# tm4.net
KiCad netlist of a schematic drawn in EAGLE
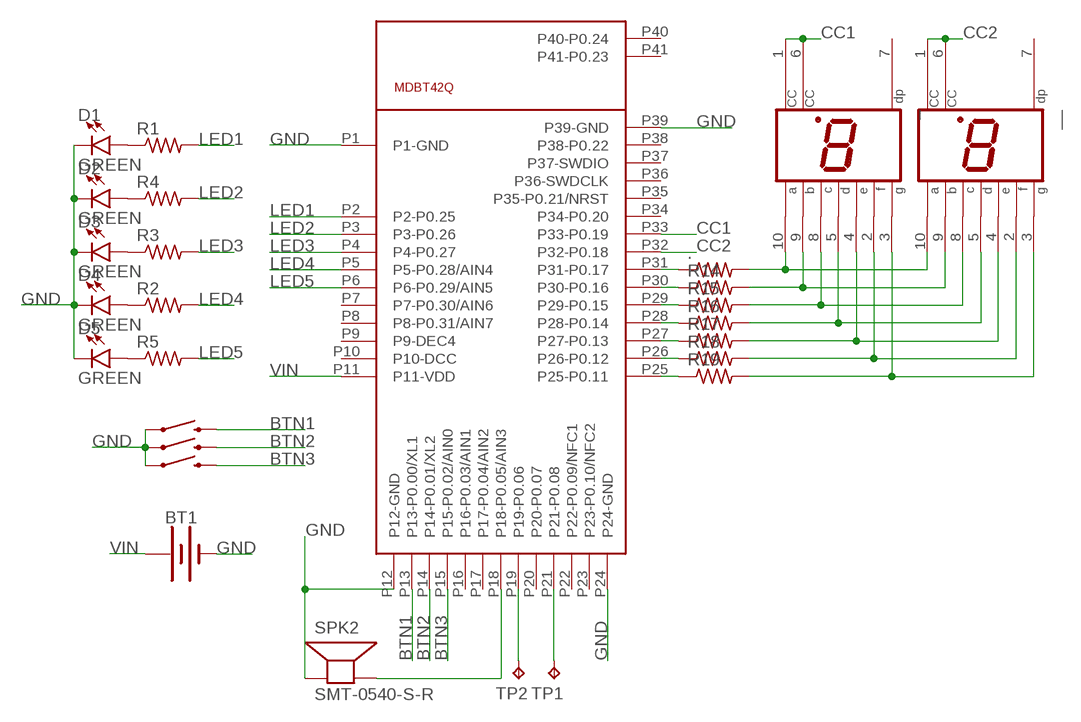
[diagram p0: schematic, sheet 1]

(export (version "E")
  (design (tool "Eeschema 10.0.6"))
  (components
    (comp (ref ".")
      (value "R-US_M0805")
      (footprint "eagle-import:M0805")
      (libsource (lib "eagle-import") (part "R-US_M0805"))
    )
    (comp (ref "BT1")
      (value "BATTERY-12MM_SMD")
      (footprint "eagle-import:BATTCON_12MM")
      (libsource (lib "eagle-import") (part "BATTERY-12MM_SMD"))
    )
    (comp (ref "D1")
      (value "GREEN")
      (footprint "eagle-import:LED-1206")
      (libsource (lib "eagle-import") (part "LED-GREEN1206"))
    )
    (comp (ref "D2")
      (value "GREEN")
      (footprint "eagle-import:LED-1206")
      (libsource (lib "eagle-import") (part "LED-GREEN1206"))
    )
    (comp (ref "D3")
      (value "GREEN")
      (footprint "eagle-import:LED-1206")
      (libsource (lib "eagle-import") (part "LED-GREEN1206"))
    )
    (comp (ref "D4")
      (value "GREEN")
      (footprint "eagle-import:LED-1206")
      (libsource (lib "eagle-import") (part "LED-GREEN1206"))
    )
    (comp (ref "D5")
      (value "GREEN")
      (footprint "eagle-import:LED-1206")
      (libsource (lib "eagle-import") (part "LED-GREEN1206"))
    )
    (comp (ref "R1")
      (value "R-US_M0805")
      (footprint "eagle-import:M0805")
      (libsource (lib "eagle-import") (part "R-US_M0805"))
    )
    (comp (ref "R2")
      (value "R-US_M0805")
      (footprint "eagle-import:M0805")
      (libsource (lib "eagle-import") (part "R-US_M0805"))
    )
    (comp (ref "R3")
      (value "R-US_M0805")
      (footprint "eagle-import:M0805")
      (libsource (lib "eagle-import") (part "R-US_M0805"))
    )
    (comp (ref "R4")
      (value "R-US_M0805")
      (footprint "eagle-import:M0805")
      (libsource (lib "eagle-import") (part "R-US_M0805"))
    )
    (comp (ref "R5")
      (value "R-US_M0805")
      (footprint "eagle-import:M0805")
      (libsource (lib "eagle-import") (part "R-US_M0805"))
    )
    (comp (ref "R14")
      (value "R-US_M0805")
      (footprint "eagle-import:M0805")
      (libsource (lib "eagle-import") (part "R-US_M0805"))
    )
    (comp (ref "R15")
      (value "R-US_M0805")
      (footprint "eagle-import:M0805")
      (libsource (lib "eagle-import") (part "R-US_M0805"))
    )
    (comp (ref "R16")
      (value "R-US_M0805")
      (footprint "eagle-import:M0805")
      (libsource (lib "eagle-import") (part "R-US_M0805"))
    )
    (comp (ref "R17")
      (value "R-US_M0805")
      (footprint "eagle-import:M0805")
      (libsource (lib "eagle-import") (part "R-US_M0805"))
    )
    (comp (ref "R18")
      (value "R-US_M0805")
      (footprint "eagle-import:M0805")
      (libsource (lib "eagle-import") (part "R-US_M0805"))
    )
    (comp (ref "R19")
      (value "R-US_M0805")
      (footprint "eagle-import:M0805")
      (libsource (lib "eagle-import") (part "R-US_M0805"))
    )
    (comp (ref "SPK2")
      (value "SMT-0540-S-R")
      (footprint "eagle-import:SMT-0540-S-R")
      (libsource (lib "eagle-import") (part "SMT-0540-S-R"))
    )
    (comp (ref "TP1")
      (value "TPTP19R")
      (footprint "eagle-import:TP19R")
      (libsource (lib "eagle-import") (part "TPTP19R"))
    )
    (comp (ref "TP2")
      (value "TPTP19R")
      (footprint "eagle-import:TP19R")
      (libsource (lib "eagle-import") (part "TPTP19R"))
    )
    (comp (ref "U$1")
      (value "MDBT42Q")
      (footprint "eagle-import:MDBT40")
      (libsource (lib "eagle-import") (part "MDBT42Q"))
    )
    (comp (ref "_")
      (value "HD-A103")
      (footprint "eagle-import:HDSP-A")
      (libsource (lib "eagle-import") (part "HD-A103"))
    )
    (comp (ref "__")
      (value "HD-A103")
      (footprint "eagle-import:HDSP-A")
      (libsource (lib "eagle-import") (part "HD-A103"))
    )
    (comp (ref "____")
      (value "MOMENTARY-SWITCH-SPST-SMD-6.2MM-TALL")
      (footprint "eagle-import:TACTILE_SWITCH_SMD_6.2MM_TALL")
      (libsource (lib "eagle-import") (part "MOMENTARY-SWITCH-SPST-SMD-6.2MM-TALL"))
    )
    (comp (ref "_____")
      (value "MOMENTARY-SWITCH-SPST-SMD-6.2MM-TALL")
      (footprint "eagle-import:TACTILE_SWITCH_SMD_6.2MM_TALL")
      (libsource (lib "eagle-import") (part "MOMENTARY-SWITCH-SPST-SMD-6.2MM-TALL"))
    )
    (comp (ref "______")
      (value "MOMENTARY-SWITCH-SPST-SMD-6.2MM-TALL")
      (footprint "eagle-import:TACTILE_SWITCH_SMD_6.2MM_TALL")
      (libsource (lib "eagle-import") (part "MOMENTARY-SWITCH-SPST-SMD-6.2MM-TALL"))
    )
  )
  (nets
    (net (code "1") (name "/BTN1") (class "Default")
      (node (ref "U$1") (pin "P13") (pinfunction "P13-P0.00/XL1_P13") (pintype "bidirectional"))
      (node (ref "____") (pin "B2") (pinfunction "2_B2") (pintype "passive"))
    )
    (net (code "2") (name "/BTN2") (class "Default")
      (node (ref "U$1") (pin "P14") (pinfunction "P14-P0.01/XL2_P14") (pintype "bidirectional"))
      (node (ref "_____") (pin "B2") (pinfunction "2_B2") (pintype "passive"))
    )
    (net (code "3") (name "/BTN3") (class "Default")
      (node (ref "U$1") (pin "P15") (pinfunction "P15-P0.02/AIN0_P15") (pintype "bidirectional"))
      (node (ref "______") (pin "B2") (pinfunction "2_B2") (pintype "passive"))
    )
    (net (code "4") (name "/CC1") (class "Default")
      (node (ref "U$1") (pin "P33") (pinfunction "P33-P0.19_P33") (pintype "bidirectional"))
      (node (ref "_") (pin "1") (pinfunction "CC_1") (pintype "passive"))
      (node (ref "_") (pin "6") (pinfunction "CC_6") (pintype "passive"))
    )
    (net (code "5") (name "/CC2") (class "Default")
      (node (ref "U$1") (pin "P32") (pinfunction "P32-P0.18_P32") (pintype "bidirectional"))
      (node (ref "__") (pin "1") (pinfunction "CC_1") (pintype "passive"))
      (node (ref "__") (pin "6") (pinfunction "CC_6") (pintype "passive"))
    )
    (net (code "6") (name "/GND") (class "Default")
      (node (ref "BT1") (pin "GND") (pinfunction "-_GND") (pintype "power_in"))
      (node (ref "D1") (pin "C") (pinfunction "C_C") (pintype "passive"))
      (node (ref "D2") (pin "C") (pinfunction "C_C") (pintype "passive"))
      (node (ref "D3") (pin "C") (pinfunction "C_C") (pintype "passive"))
      (node (ref "D4") (pin "C") (pinfunction "C_C") (pintype "passive"))
      (node (ref "D5") (pin "C") (pinfunction "C_C") (pintype "passive"))
      (node (ref "SPK2") (pin "-") (pinfunction "+_-") (pintype "passive"))
      (node (ref "U$1") (pin "P1") (pinfunction "P1-GND_P1") (pintype "bidirectional"))
      (node (ref "U$1") (pin "P12") (pinfunction "P12-GND_P12") (pintype "bidirectional"))
      (node (ref "U$1") (pin "P24") (pinfunction "P24-GND_P24") (pintype "bidirectional"))
      (node (ref "U$1") (pin "P39") (pinfunction "P39-GND_P39") (pintype "bidirectional"))
      (node (ref "____") (pin "A2") (pinfunction "1_A2") (pintype "passive"))
      (node (ref "_____") (pin "A2") (pinfunction "1_A2") (pintype "passive"))
      (node (ref "______") (pin "A2") (pinfunction "1_A2") (pintype "passive"))
    )
    (net (code "7") (name "/LED1") (class "Default")
      (node (ref "R1") (pin "2") (pinfunction "2_2") (pintype "passive"))
      (node (ref "U$1") (pin "P2") (pinfunction "P2-P0.25_P2") (pintype "bidirectional"))
    )
    (net (code "8") (name "/LED2") (class "Default")
      (node (ref "R4") (pin "2") (pinfunction "2_2") (pintype "passive"))
      (node (ref "U$1") (pin "P3") (pinfunction "P3-P0.26_P3") (pintype "bidirectional"))
    )
    (net (code "9") (name "/LED3") (class "Default")
      (node (ref "R3") (pin "2") (pinfunction "2_2") (pintype "passive"))
      (node (ref "U$1") (pin "P4") (pinfunction "P4-P0.27_P4") (pintype "bidirectional"))
    )
    (net (code "10") (name "/LED4") (class "Default")
      (node (ref "R2") (pin "2") (pinfunction "2_2") (pintype "passive"))
      (node (ref "U$1") (pin "P5") (pinfunction "P5-P0.28/AIN4_P5") (pintype "bidirectional"))
    )
    (net (code "11") (name "/LED5") (class "Default")
      (node (ref "R5") (pin "2") (pinfunction "2_2") (pintype "passive"))
      (node (ref "U$1") (pin "P6") (pinfunction "P6-P0.29/AIN5_P6") (pintype "bidirectional"))
    )
    (net (code "12") (name "/VIN") (class "Default")
      (node (ref "BT1") (pin "PWR@1") (pinfunction "+_PWR@1") (pintype "power_in"))
      (node (ref "U$1") (pin "P11") (pinfunction "P11-VDD_P11") (pintype "bidirectional"))
    )
    (net (code "13") (name "Net-(D1-PadA)") (class "Default")
      (node (ref "D1") (pin "A") (pinfunction "A_A") (pintype "passive"))
      (node (ref "R1") (pin "1") (pinfunction "1_1") (pintype "passive"))
    )
    (net (code "14") (name "Net-(D2-PadA)") (class "Default")
      (node (ref "D2") (pin "A") (pinfunction "A_A") (pintype "passive"))
      (node (ref "R4") (pin "1") (pinfunction "1_1") (pintype "passive"))
    )
    (net (code "15") (name "Net-(D3-PadA)") (class "Default")
      (node (ref "D3") (pin "A") (pinfunction "A_A") (pintype "passive"))
      (node (ref "R3") (pin "1") (pinfunction "1_1") (pintype "passive"))
    )
    (net (code "16") (name "Net-(D4-PadA)") (class "Default")
      (node (ref "D4") (pin "A") (pinfunction "A_A") (pintype "passive"))
      (node (ref "R2") (pin "1") (pinfunction "1_1") (pintype "passive"))
    )
    (net (code "17") (name "Net-(D5-PadA)") (class "Default")
      (node (ref "D5") (pin "A") (pinfunction "A_A") (pintype "passive"))
      (node (ref "R5") (pin "1") (pinfunction "1_1") (pintype "passive"))
    )
    (net (code "18") (name "Net-(SPK2--)") (class "Default")
      (node (ref "SPK2") (pin "+") (pinfunction "-_+") (pintype "passive"))
      (node (ref "U$1") (pin "P18") (pinfunction "P18-P0.05/AIN3_P18") (pintype "bidirectional"))
    )
    (net (code "19") (name "Net-(U$1-P19-P0.06)") (class "Default")
      (node (ref "TP2") (pin "TP") (pinfunction "TP_TP") (pintype "input"))
      (node (ref "U$1") (pin "P19") (pinfunction "P19-P0.06_P19") (pintype "bidirectional"))
    )
    (net (code "20") (name "Net-(U$1-P21-P0.08)") (class "Default")
      (node (ref "TP1") (pin "TP") (pinfunction "TP_TP") (pintype "input"))
      (node (ref "U$1") (pin "P21") (pinfunction "P21-P0.08_P21") (pintype "bidirectional"))
    )
    (net (code "21") (name "Net-(U$1-P25-P0.11)") (class "Default")
      (node (ref "R19") (pin "1") (pinfunction "1_1") (pintype "passive"))
      (node (ref "U$1") (pin "P25") (pinfunction "P25-P0.11_P25") (pintype "bidirectional"))
    )
    (net (code "22") (name "Net-(U$1-P26-P0.12)") (class "Default")
      (node (ref "R18") (pin "1") (pinfunction "1_1") (pintype "passive"))
      (node (ref "U$1") (pin "P26") (pinfunction "P26-P0.12_P26") (pintype "bidirectional"))
    )
    (net (code "23") (name "Net-(U$1-P27-P0.13)") (class "Default")
      (node (ref "R17") (pin "1") (pinfunction "1_1") (pintype "passive"))
      (node (ref "U$1") (pin "P27") (pinfunction "P27-P0.13_P27") (pintype "bidirectional"))
    )
    (net (code "24") (name "Net-(U$1-P28-P0.14)") (class "Default")
      (node (ref "R16") (pin "1") (pinfunction "1_1") (pintype "passive"))
      (node (ref "U$1") (pin "P28") (pinfunction "P28-P0.14_P28") (pintype "bidirectional"))
    )
    (net (code "25") (name "Net-(U$1-P29-P0.15)") (class "Default")
      (node (ref "R15") (pin "1") (pinfunction "1_1") (pintype "passive"))
      (node (ref "U$1") (pin "P29") (pinfunction "P29-P0.15_P29") (pintype "bidirectional"))
    )
    (net (code "26") (name "Net-(U$1-P30-P0.16)") (class "Default")
      (node (ref "R14") (pin "1") (pinfunction "1_1") (pintype "passive"))
      (node (ref "U$1") (pin "P30") (pinfunction "P30-P0.16_P30") (pintype "bidirectional"))
    )
    (net (code "27") (name "Net-(U$1-P31-P0.17)") (class "Default")
      (node (ref ".") (pin "1") (pinfunction "1_1") (pintype "passive"))
      (node (ref "U$1") (pin "P31") (pinfunction "P31-P0.17_P31") (pintype "bidirectional"))
    )
    (net (code "28") (name "Net-(_-A)") (class "Default")
      (node (ref ".") (pin "2") (pinfunction "2_2") (pintype "passive"))
      (node (ref "_") (pin "10") (pinfunction "A_10") (pintype "passive"))
      (node (ref "__") (pin "10") (pinfunction "A_10") (pintype "passive"))
    )
    (net (code "29") (name "Net-(_-B)") (class "Default")
      (node (ref "R14") (pin "2") (pinfunction "2_2") (pintype "passive"))
      (node (ref "_") (pin "9") (pinfunction "B_9") (pintype "passive"))
      (node (ref "__") (pin "9") (pinfunction "B_9") (pintype "passive"))
    )
    (net (code "30") (name "Net-(_-C)") (class "Default")
      (node (ref "R15") (pin "2") (pinfunction "2_2") (pintype "passive"))
      (node (ref "_") (pin "8") (pinfunction "C_8") (pintype "passive"))
      (node (ref "__") (pin "8") (pinfunction "C_8") (pintype "passive"))
    )
    (net (code "31") (name "Net-(_-D)") (class "Default")
      (node (ref "R16") (pin "2") (pinfunction "2_2") (pintype "passive"))
      (node (ref "_") (pin "5") (pinfunction "D_5") (pintype "passive"))
      (node (ref "__") (pin "5") (pinfunction "D_5") (pintype "passive"))
    )
    (net (code "32") (name "Net-(_-E)") (class "Default")
      (node (ref "R17") (pin "2") (pinfunction "2_2") (pintype "passive"))
      (node (ref "_") (pin "4") (pinfunction "E_4") (pintype "passive"))
      (node (ref "__") (pin "4") (pinfunction "E_4") (pintype "passive"))
    )
    (net (code "33") (name "Net-(_-F)") (class "Default")
      (node (ref "R18") (pin "2") (pinfunction "2_2") (pintype "passive"))
      (node (ref "_") (pin "2") (pinfunction "F_2") (pintype "passive"))
      (node (ref "__") (pin "2") (pinfunction "F_2") (pintype "passive"))
    )
    (net (code "34") (name "Net-(_-G)") (class "Default")
      (node (ref "R19") (pin "2") (pinfunction "2_2") (pintype "passive"))
      (node (ref "_") (pin "3") (pinfunction "G_3") (pintype "passive"))
      (node (ref "__") (pin "3") (pinfunction "G_3") (pintype "passive"))
    )
    (net (code "35") (name "unconnected-(U$1-P7-P0.30{slash}AIN6-PadP7)") (class "Default")
      (node (ref "U$1") (pin "P7") (pinfunction "P7-P0.30/AIN6_P7") (pintype "bidirectional"))
    )
    (net (code "36") (name "unconnected-(U$1-P8-P0.31{slash}AIN7-PadP8)") (class "Default")
      (node (ref "U$1") (pin "P8") (pinfunction "P8-P0.31/AIN7_P8") (pintype "bidirectional"))
    )
    (net (code "37") (name "unconnected-(U$1-P9-DEC4-PadP9)") (class "Default")
      (node (ref "U$1") (pin "P9") (pinfunction "P9-DEC4_P9") (pintype "bidirectional"))
    )
    (net (code "38") (name "unconnected-(U$1-P10-DCC-PadP10)") (class "Default")
      (node (ref "U$1") (pin "P10") (pinfunction "P10-DCC_P10") (pintype "bidirectional"))
    )
    (net (code "39") (name "unconnected-(U$1-P16-P0.03{slash}AIN1-PadP16)") (class "Default")
      (node (ref "U$1") (pin "P16") (pinfunction "P16-P0.03/AIN1_P16") (pintype "bidirectional"))
    )
    (net (code "40") (name "unconnected-(U$1-P17-P0.04{slash}AIN2-PadP17)") (class "Default")
      (node (ref "U$1") (pin "P17") (pinfunction "P17-P0.04/AIN2_P17") (pintype "bidirectional"))
    )
    (net (code "41") (name "unconnected-(U$1-P20-P0.07-PadP20)") (class "Default")
      (node (ref "U$1") (pin "P20") (pinfunction "P20-P0.07_P20") (pintype "bidirectional"))
    )
    (net (code "42") (name "unconnected-(U$1-P22-P0.09{slash}NFC1-PadP22)") (class "Default")
      (node (ref "U$1") (pin "P22") (pinfunction "P22-P0.09/NFC1_P22") (pintype "bidirectional"))
    )
    (net (code "43") (name "unconnected-(U$1-P23-P0.10{slash}NFC2-PadP23)") (class "Default")
      (node (ref "U$1") (pin "P23") (pinfunction "P23-P0.10/NFC2_P23") (pintype "bidirectional"))
    )
    (net (code "44") (name "unconnected-(U$1-P34-P0.20-PadP34)") (class "Default")
      (node (ref "U$1") (pin "P34") (pinfunction "P34-P0.20_P34") (pintype "bidirectional"))
    )
    (net (code "45") (name "unconnected-(U$1-P35-P0.21{slash}NRST-PadP35)") (class "Default")
      (node (ref "U$1") (pin "P35") (pinfunction "P35-P0.21/NRST_P35") (pintype "bidirectional"))
    )
    (net (code "46") (name "unconnected-(U$1-P36-SWDCLK-PadP36)") (class "Default")
      (node (ref "U$1") (pin "P36") (pinfunction "P36-SWDCLK_P36") (pintype "bidirectional"))
    )
    (net (code "47") (name "unconnected-(U$1-P37-SWDIO-PadP37)") (class "Default")
      (node (ref "U$1") (pin "P37") (pinfunction "P37-SWDIO_P37") (pintype "bidirectional"))
    )
    (net (code "48") (name "unconnected-(U$1-P38-P0.22-PadP38)") (class "Default")
      (node (ref "U$1") (pin "P38") (pinfunction "P38-P0.22_P38") (pintype "bidirectional"))
    )
    (net (code "49") (name "unconnected-(U$1-P40-P0.24-PadP40)") (class "Default")
      (node (ref "U$1") (pin "P40") (pinfunction "P40-P0.24_P40") (pintype "bidirectional"))
    )
    (net (code "50") (name "unconnected-(U$1-P41-P0.23-PadP41)") (class "Default")
      (node (ref "U$1") (pin "P41") (pinfunction "P41-P0.23_P41") (pintype "bidirectional"))
    )
    (net (code "51") (name "unconnected-(_-DP-Pad7)") (class "Default")
      (node (ref "_") (pin "7") (pinfunction "DP_7") (pintype "passive"))
    )
    (net (code "52") (name "unconnected-(__-DP-Pad7)") (class "Default")
      (node (ref "__") (pin "7") (pinfunction "DP_7") (pintype "passive"))
    )
  )
)
